# Linear_Slider.net
KiCad netlist of a schematic drawn in EAGLE
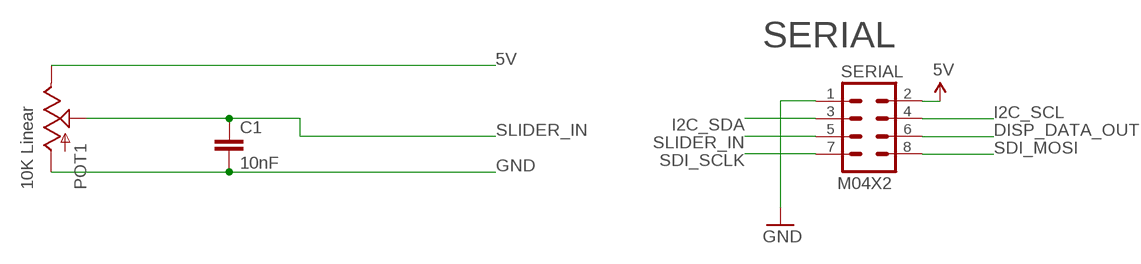
[diagram p0: schematic, sheet 1]

(export (version "E")
  (design (tool "Eeschema 10.0.6"))
  (components
    (comp (ref "C1")
      (value "10nF")
      (footprint "eagle-import:0603-CAP")
      (libsource (lib "eagle-import") (part "CAP0603-CAP"))
    )
    (comp (ref "POT1")
      (value "10K Linear")
      (footprint "eagle-import:SLIDER60")
      (libsource (lib "eagle-import") (part "SLIDER60"))
    )
    (comp (ref "SERIAL")
      (value "M04X2")
      (footprint "eagle-import:2X4")
      (libsource (lib "eagle-import") (part "M04X2"))
    )
  )
  (nets
    (net (code "1") (name "/DISP_DATA_OUT") (class "Default")
      (node (ref "SERIAL") (pin "6") (pinfunction "6_6") (pintype "passive"))
    )
    (net (code "2") (name "/I2C_SCL") (class "Default")
      (node (ref "SERIAL") (pin "4") (pinfunction "4_4") (pintype "passive"))
    )
    (net (code "3") (name "/I2C_SDA") (class "Default")
      (node (ref "SERIAL") (pin "3") (pinfunction "3_3") (pintype "passive"))
    )
    (net (code "4") (name "/SDI_MOSI") (class "Default")
      (node (ref "SERIAL") (pin "8") (pinfunction "8_8") (pintype "passive"))
    )
    (net (code "5") (name "/SDI_SCLK") (class "Default")
      (node (ref "SERIAL") (pin "7") (pinfunction "7_7") (pintype "passive"))
    )
    (net (code "6") (name "/SLIDER_IN") (class "Default")
      (node (ref "C1") (pin "1") (pinfunction "1_1") (pintype "passive"))
      (node (ref "POT1") (pin "2A") (pinfunction "S_2A") (pintype "passive"))
      (node (ref "SERIAL") (pin "5") (pinfunction "5_5") (pintype "passive"))
    )
    (net (code "7") (name "5V") (class "Default")
      (node (ref "POT1") (pin "1") (pinfunction "E_1") (pintype "passive"))
      (node (ref "SERIAL") (pin "2") (pinfunction "2_2") (pintype "passive"))
    )
    (net (code "8") (name "GND") (class "Default")
      (node (ref "C1") (pin "2") (pinfunction "2_2") (pintype "passive"))
      (node (ref "POT1") (pin "3") (pinfunction "A_3") (pintype "passive"))
      (node (ref "SERIAL") (pin "1") (pinfunction "1_1") (pintype "passive"))
    )
  )
)
